# phase.net
KiCad netlist of a schematic drawn in EAGLE
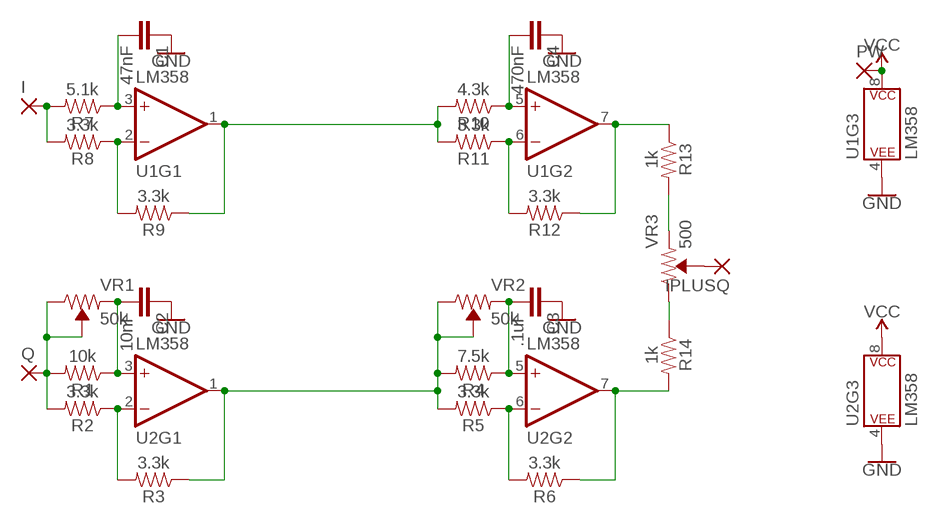
[diagram p0: schematic, sheet 1]

(export (version "E")
  (design (tool "Eeschema 10.0.6"))
  (components
    (comp (ref "C1")
      (value "47nF")
      (footprint "eagle-import:C5B3.5")
      (libsource (lib "eagle-import") (part "C5/3.5"))
    )
    (comp (ref "C2")
      (value "10nF")
      (footprint "eagle-import:C5B3.5")
      (libsource (lib "eagle-import") (part "C5/3.5"))
    )
    (comp (ref "C3")
      (value ".1uF")
      (footprint "eagle-import:C5B3.5")
      (libsource (lib "eagle-import") (part "C5/3.5"))
    )
    (comp (ref "C4")
      (value "470nF")
      (footprint "eagle-import:C5B3.5")
      (libsource (lib "eagle-import") (part "C5/3.5"))
    )
    (comp (ref "I")
      (value "2,54/1,1")
      (footprint "eagle-import:2,54_1,1")
      (libsource (lib "eagle-import") (part "2,54/1,1"))
    )
    (comp (ref "IPLUSQ")
      (value "2,54/1,1")
      (footprint "eagle-import:2,54_1,1")
      (libsource (lib "eagle-import") (part "2,54/1,1"))
    )
    (comp (ref "PW")
      (value "2,54/1,1")
      (footprint "eagle-import:2,54_1,1")
      (libsource (lib "eagle-import") (part "2,54/1,1"))
    )
    (comp (ref "Q")
      (value "2,54/1,1")
      (footprint "eagle-import:2,54_1,1")
      (libsource (lib "eagle-import") (part "2,54/1,1"))
    )
    (comp (ref "R1")
      (value "10k")
      (footprint "eagle-import:AXIAL-0.3")
      (libsource (lib "eagle-import") (part "1KOHM-HORIZ-1/4W-1%"))
    )
    (comp (ref "R2")
      (value "3.3k")
      (footprint "eagle-import:AXIAL-0.3")
      (libsource (lib "eagle-import") (part "1KOHM-HORIZ-1/4W-1%"))
    )
    (comp (ref "R3")
      (value "3.3k")
      (footprint "eagle-import:AXIAL-0.3")
      (libsource (lib "eagle-import") (part "1KOHM-HORIZ-1/4W-1%"))
    )
    (comp (ref "R4")
      (value "7.5k")
      (footprint "eagle-import:AXIAL-0.3")
      (libsource (lib "eagle-import") (part "1KOHM-HORIZ-1/4W-1%"))
    )
    (comp (ref "R5")
      (value "3.3k")
      (footprint "eagle-import:AXIAL-0.3")
      (libsource (lib "eagle-import") (part "1KOHM-HORIZ-1/4W-1%"))
    )
    (comp (ref "R6")
      (value "3.3k")
      (footprint "eagle-import:AXIAL-0.3")
      (libsource (lib "eagle-import") (part "1KOHM-HORIZ-1/4W-1%"))
    )
    (comp (ref "R7")
      (value "5.1k")
      (footprint "eagle-import:AXIAL-0.3")
      (libsource (lib "eagle-import") (part "1KOHM-HORIZ-1/4W-1%"))
    )
    (comp (ref "R8")
      (value "3.3k")
      (footprint "eagle-import:AXIAL-0.3")
      (libsource (lib "eagle-import") (part "1KOHM-HORIZ-1/4W-1%"))
    )
    (comp (ref "R9")
      (value "3.3k")
      (footprint "eagle-import:AXIAL-0.3")
      (libsource (lib "eagle-import") (part "1KOHM-HORIZ-1/4W-1%"))
    )
    (comp (ref "R10")
      (value "4.3k")
      (footprint "eagle-import:AXIAL-0.3")
      (libsource (lib "eagle-import") (part "1KOHM-HORIZ-1/4W-1%"))
    )
    (comp (ref "R11")
      (value "3.3k")
      (footprint "eagle-import:AXIAL-0.3")
      (libsource (lib "eagle-import") (part "1KOHM-HORIZ-1/4W-1%"))
    )
    (comp (ref "R12")
      (value "3.3k")
      (footprint "eagle-import:AXIAL-0.3")
      (libsource (lib "eagle-import") (part "1KOHM-HORIZ-1/4W-1%"))
    )
    (comp (ref "R13")
      (value "1k")
      (footprint "eagle-import:AXIAL-0.3")
      (libsource (lib "eagle-import") (part "1KOHM-HORIZ-1/4W-1%"))
    )
    (comp (ref "R14")
      (value "1k")
      (footprint "eagle-import:AXIAL-0.3")
      (libsource (lib "eagle-import") (part "1KOHM-HORIZ-1/4W-1%"))
    )
    (comp (ref "U1")
      (value "LM358")
      (footprint "eagle-import:DIP08")
      (libsource (lib "eagle-import") (part "LM358"))
    )
    (comp (ref "U2")
      (value "LM358")
      (footprint "eagle-import:DIP08")
      (libsource (lib "eagle-import") (part "LM358"))
    )
    (comp (ref "VR1")
      (value "50k")
      (footprint "eagle-import:TRIMPOT-PTH-3386U")
      (libsource (lib "eagle-import") (part "TRIMPOT-PTH-10MM-KNOB-1/2W-10%"))
    )
    (comp (ref "VR2")
      (value "50k")
      (footprint "eagle-import:TRIMPOT-PTH-3386U")
      (libsource (lib "eagle-import") (part "TRIMPOT-PTH-10MM-KNOB-1/2W-10%"))
    )
    (comp (ref "VR3")
      (value "500")
      (footprint "eagle-import:TRIMPOT-PTH-3386U")
      (libsource (lib "eagle-import") (part "TRIMPOT-PTH-10MM-KNOB-1/2W-10%"))
    )
  )
  (nets
    (net (code "1") (name "GND") (class "Default")
      (node (ref "C1") (pin "1") (pinfunction "1_1") (pintype "passive"))
      (node (ref "C2") (pin "1") (pinfunction "1_1") (pintype "passive"))
      (node (ref "C3") (pin "1") (pinfunction "1_1") (pintype "passive"))
      (node (ref "C4") (pin "1") (pinfunction "1_1") (pintype "passive"))
      (node (ref "U1") (pin "4") (pinfunction "P$V-_4") (pintype "bidirectional"))
      (node (ref "U2") (pin "4") (pinfunction "P$V-_4") (pintype "bidirectional"))
    )
    (net (code "2") (name "Net-(I-P)") (class "Default")
      (node (ref "I") (pin "1") (pinfunction "P_1") (pintype "passive"))
      (node (ref "R7") (pin "P$2") (pinfunction "2_P$2") (pintype "passive"))
      (node (ref "R8") (pin "P$2") (pinfunction "2_P$2") (pintype "passive"))
    )
    (net (code "3") (name "Net-(IPLUSQ-P)") (class "Default")
      (node (ref "IPLUSQ") (pin "1") (pinfunction "P_1") (pintype "passive"))
      (node (ref "VR3") (pin "2") (pinfunction "WIPER_2") (pintype "passive"))
    )
    (net (code "4") (name "Net-(Q-P)") (class "Default")
      (node (ref "Q") (pin "1") (pinfunction "P_1") (pintype "passive"))
      (node (ref "R1") (pin "P$2") (pinfunction "2_P$2") (pintype "passive"))
      (node (ref "R2") (pin "P$2") (pinfunction "2_P$2") (pintype "passive"))
      (node (ref "VR1") (pin "2") (pinfunction "WIPER_2") (pintype "passive"))
      (node (ref "VR1") (pin "3") (pinfunction "CW_3") (pintype "passive"))
    )
    (net (code "5") (name "Net-(R1-1)") (class "Default")
      (node (ref "C2") (pin "2") (pinfunction "2_2") (pintype "passive"))
      (node (ref "R1") (pin "P$1") (pinfunction "1_P$1") (pintype "passive"))
      (node (ref "U2") (pin "3") (pinfunction "+IN_3") (pintype "input"))
      (node (ref "VR1") (pin "1") (pinfunction "CCW_1") (pintype "passive"))
    )
    (net (code "6") (name "Net-(R2-1)") (class "Default")
      (node (ref "R2") (pin "P$1") (pinfunction "1_P$1") (pintype "passive"))
      (node (ref "R3") (pin "P$2") (pinfunction "2_P$2") (pintype "passive"))
      (node (ref "U2") (pin "2") (pinfunction "-IN_2") (pintype "input"))
    )
    (net (code "7") (name "Net-(R3-1)") (class "Default")
      (node (ref "R3") (pin "P$1") (pinfunction "1_P$1") (pintype "passive"))
      (node (ref "R4") (pin "P$2") (pinfunction "2_P$2") (pintype "passive"))
      (node (ref "R5") (pin "P$2") (pinfunction "2_P$2") (pintype "passive"))
      (node (ref "U2") (pin "1") (pinfunction "OUT_1") (pintype "output"))
      (node (ref "VR2") (pin "2") (pinfunction "WIPER_2") (pintype "passive"))
      (node (ref "VR2") (pin "3") (pinfunction "CW_3") (pintype "passive"))
    )
    (net (code "8") (name "Net-(R4-1)") (class "Default")
      (node (ref "C3") (pin "2") (pinfunction "2_2") (pintype "passive"))
      (node (ref "R4") (pin "P$1") (pinfunction "1_P$1") (pintype "passive"))
      (node (ref "U2") (pin "5") (pinfunction "+IN_5") (pintype "input"))
      (node (ref "VR2") (pin "1") (pinfunction "CCW_1") (pintype "passive"))
    )
    (net (code "9") (name "Net-(R5-1)") (class "Default")
      (node (ref "R5") (pin "P$1") (pinfunction "1_P$1") (pintype "passive"))
      (node (ref "R6") (pin "P$2") (pinfunction "2_P$2") (pintype "passive"))
      (node (ref "U2") (pin "6") (pinfunction "-IN_6") (pintype "input"))
    )
    (net (code "10") (name "Net-(R7-1)") (class "Default")
      (node (ref "C1") (pin "2") (pinfunction "2_2") (pintype "passive"))
      (node (ref "R7") (pin "P$1") (pinfunction "1_P$1") (pintype "passive"))
      (node (ref "U1") (pin "3") (pinfunction "+IN_3") (pintype "input"))
    )
    (net (code "11") (name "Net-(R8-1)") (class "Default")
      (node (ref "R8") (pin "P$1") (pinfunction "1_P$1") (pintype "passive"))
      (node (ref "R9") (pin "P$2") (pinfunction "2_P$2") (pintype "passive"))
      (node (ref "U1") (pin "2") (pinfunction "-IN_2") (pintype "input"))
    )
    (net (code "12") (name "Net-(R10-1)") (class "Default")
      (node (ref "C4") (pin "2") (pinfunction "2_2") (pintype "passive"))
      (node (ref "R10") (pin "P$1") (pinfunction "1_P$1") (pintype "passive"))
      (node (ref "U1") (pin "5") (pinfunction "+IN_5") (pintype "input"))
    )
    (net (code "13") (name "Net-(R10-2)") (class "Default")
      (node (ref "R10") (pin "P$2") (pinfunction "2_P$2") (pintype "passive"))
      (node (ref "R11") (pin "P$2") (pinfunction "2_P$2") (pintype "passive"))
      (node (ref "R9") (pin "P$1") (pinfunction "1_P$1") (pintype "passive"))
      (node (ref "U1") (pin "1") (pinfunction "OUT_1") (pintype "output"))
    )
    (net (code "14") (name "Net-(R11-1)") (class "Default")
      (node (ref "R11") (pin "P$1") (pinfunction "1_P$1") (pintype "passive"))
      (node (ref "R12") (pin "P$2") (pinfunction "2_P$2") (pintype "passive"))
      (node (ref "U1") (pin "6") (pinfunction "-IN_6") (pintype "input"))
    )
    (net (code "15") (name "Net-(R12-1)") (class "Default")
      (node (ref "R12") (pin "P$1") (pinfunction "1_P$1") (pintype "passive"))
      (node (ref "R13") (pin "P$1") (pinfunction "1_P$1") (pintype "passive"))
      (node (ref "U1") (pin "7") (pinfunction "OUT_7") (pintype "output"))
    )
    (net (code "16") (name "Net-(R13-2)") (class "Default")
      (node (ref "R13") (pin "P$2") (pinfunction "2_P$2") (pintype "passive"))
      (node (ref "VR3") (pin "1") (pinfunction "CCW_1") (pintype "passive"))
    )
    (net (code "17") (name "Net-(R14-1)") (class "Default")
      (node (ref "R14") (pin "P$1") (pinfunction "1_P$1") (pintype "passive"))
      (node (ref "VR3") (pin "3") (pinfunction "CW_3") (pintype "passive"))
    )
    (net (code "18") (name "Net-(R14-2)") (class "Default")
      (node (ref "R14") (pin "P$2") (pinfunction "2_P$2") (pintype "passive"))
      (node (ref "R6") (pin "P$1") (pinfunction "1_P$1") (pintype "passive"))
      (node (ref "U2") (pin "7") (pinfunction "OUT_7") (pintype "output"))
    )
    (net (code "19") (name "VCC") (class "Default")
      (node (ref "PW") (pin "1") (pinfunction "P_1") (pintype "passive"))
      (node (ref "U1") (pin "8") (pinfunction "P$V+_8") (pintype "bidirectional"))
      (node (ref "U2") (pin "8") (pinfunction "P$V+_8") (pintype "bidirectional"))
    )
  )
)
